# STM32.net
KiCad netlist of a schematic drawn in Altium Designer
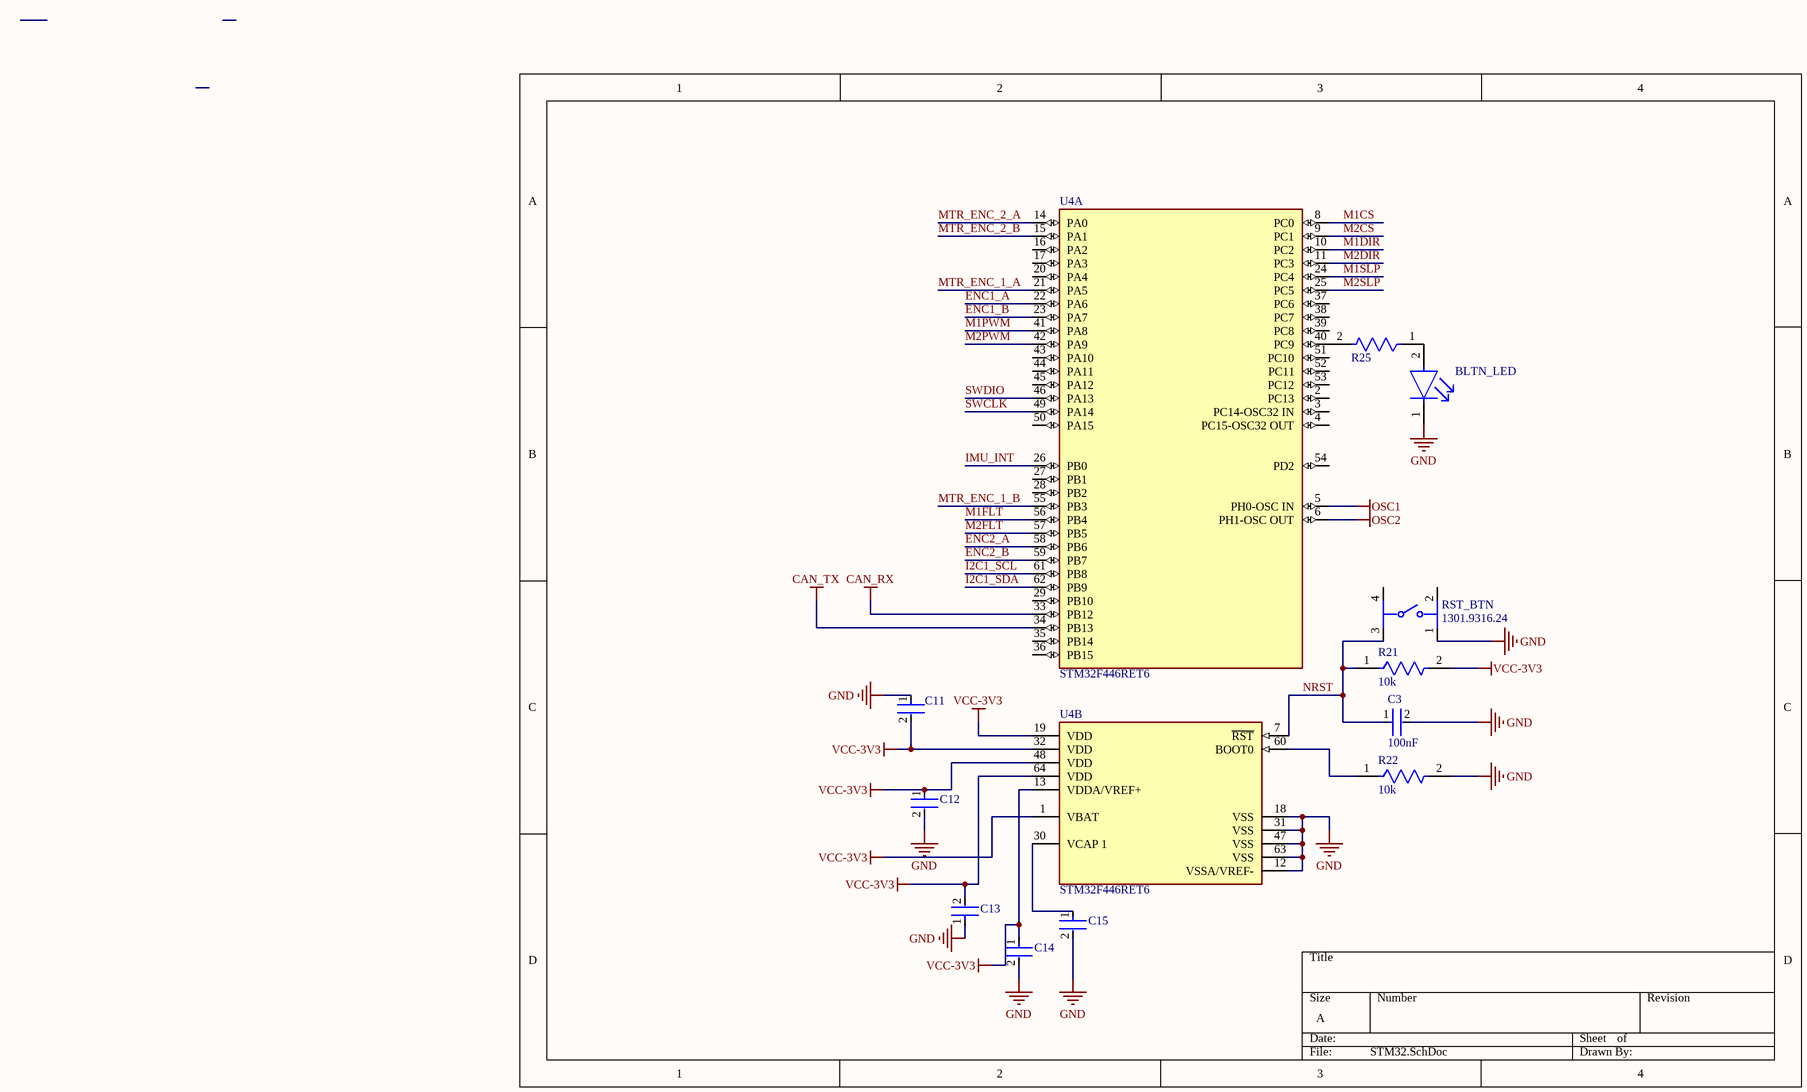
[diagram p0: STM32.SchDoc]

(export (version "E")
  (design (tool "Eeschema 10.0.6"))
  (components
    (comp (ref "BLTN_LED")
      (value "APHCM2012CGCK-F01")
      (footprint "FP-APHCM2012CGCK-F01-MFG")
      (description "LED GREEN CLEAR CHIP SMD")
      (libsource (lib "Altium Content Vault") (part "8706943c75ba83719d021d2fdc84c58"))
    )
    (comp (ref "C3")
      (value "100nF")
      (footprint "FP-0402B104K160CT-IPC_C")
      (description "CAP CER 0.1UF 16V X7R 0402")
      (fields (field (name "TOLERANCE") "10%"))
      (libsource (lib "Altium Content Vault") (part "b4654b650e69147ec39a6b967a45e02"))
    )
    (comp (ref "C11")
      (value "CC0603KRX7R9BB104")
      (footprint "FP-CC0603-DA-MFG")
      (description "CAP CER 0.1UF 50V X7R 0603")
      (fields (field (name "MANUFACTURER") "YAGEO") (field (name "VOLTAGE") "50 V"))
      (libsource (lib "Altium Content Vault") (part "11868f565c42a9108669ba33697ecf6"))
    )
    (comp (ref "C12")
      (value "CC0603KRX7R9BB104")
      (footprint "FP-CC0603-DA-MFG")
      (description "CAP CER 0.1UF 50V X7R 0603")
      (fields (field (name "MANUFACTURER") "YAGEO") (field (name "VOLTAGE") "50 V"))
      (libsource (lib "Altium Content Vault") (part "11868f565c42a9108669ba33697ecf6"))
    )
    (comp (ref "C13")
      (value "CC0603KRX7R9BB104")
      (footprint "FP-CC0603-DA-MFG")
      (description "CAP CER 0.1UF 50V X7R 0603")
      (fields (field (name "MANUFACTURER") "YAGEO") (field (name "VOLTAGE") "50 V"))
      (libsource (lib "Altium Content Vault") (part "11868f565c42a9108669ba33697ecf6"))
    )
    (comp (ref "C14")
      (value "CC0603KRX7R9BB104")
      (footprint "FP-CC0603-DA-MFG")
      (description "CAP CER 0.1UF 50V X7R 0603")
      (fields (field (name "MANUFACTURER") "YAGEO") (field (name "VOLTAGE") "50 V"))
      (libsource (lib "Altium Content Vault") (part "11868f565c42a9108669ba33697ecf6"))
    )
    (comp (ref "C15")
      (value "CL10A475KP8NNNC")
      (footprint "FP-CL10-IPC_C")
      (description "Cap Ceramic 4.7uF 10V X5R ±10% Pad SMD 0603 +85°C T/R")
      (fields (field (name "TOLERANCE") "10%"))
      (libsource (lib "Altium Content Vault") (part "b4654b650e69147ec39a6b967a45e02"))
    )
    (comp (ref "R21")
      (value "10k")
      (footprint "FP-RC0603-0_55-IPC_C")
      (description "RES 10K OHM 1% 1/10W 0603")
      (fields (field (name "TOLERANCE") "1%"))
      (libsource (lib "Altium Content Vault") (part "1029c3af85768c4190bb7ad29bc67b5"))
    )
    (comp (ref "R22")
      (value "10k")
      (footprint "FP-RC0603-0_55-IPC_C")
      (description "RES 10K OHM 1% 1/10W 0603")
      (fields (field (name "TOLERANCE") "1%"))
      (libsource (lib "Altium Content Vault") (part "1029c3af85768c4190bb7ad29bc67b5"))
    )
    (comp (ref "R25")
      (value "AC0603FR-10470RL")
      (footprint "FP-AC0603-IPC_A")
      (description "RES 470Ω 1.00% 0.1W 0603")
      (fields (field (name "TOLERANCE") "1%"))
      (libsource (lib "Altium Content Vault") (part "1029c3af85768c4190bb7ad29bc67b5"))
    )
    (comp (ref "RST_BTN")
      (value "1301.9316.24")
      (footprint "FP-1301_9316_24-MFG")
      (description "LSH 6X6 SHORT TRAVEL SWITCH 7.00")
      (libsource (lib "Altium Content Vault") (part "c0df99d12937e9d2da15afdedf14b17"))
    )
    (comp (ref "U4")
      (value "STM32F446RET6")
      (footprint "FP-LQFP64-5W-MFG")
      (description "IC MCU 32BIT 512KB FLASH 64LQFP")
      (fields
        (field (name "OCTOPART") "https://octopart.com/stm32f446ret6-stmicroelectronics-52642920")
        (field (name "MANUFACTURER") "ST")
      )
      (libsource (lib "Altium Content Vault") (part "ee11adc32c0ab33b933cccf4348c338"))
    )
  )
  (nets
    (net (code "1") (name "/ENC1_A") (class "Default")
      (node (ref "U4") (pin "22") (pinfunction "PA6_22") (pintype "bidirectional"))
    )
    (net (code "2") (name "/ENC1_B") (class "Default")
      (node (ref "U4") (pin "23") (pinfunction "PA7_23") (pintype "bidirectional"))
    )
    (net (code "3") (name "/ENC2_A") (class "Default")
      (node (ref "U4") (pin "58") (pinfunction "PB6_58") (pintype "bidirectional"))
    )
    (net (code "4") (name "/ENC2_B") (class "Default")
      (node (ref "U4") (pin "59") (pinfunction "PB7_59") (pintype "bidirectional"))
    )
    (net (code "5") (name "/I2C1_SCL") (class "Default")
      (node (ref "U4") (pin "61") (pinfunction "PB8_61") (pintype "bidirectional"))
    )
    (net (code "6") (name "/I2C1_SDA") (class "Default")
      (node (ref "U4") (pin "62") (pinfunction "PB9_62") (pintype "bidirectional"))
    )
    (net (code "7") (name "/IMU_INT") (class "Default")
      (node (ref "U4") (pin "26") (pinfunction "PB0_26") (pintype "bidirectional"))
    )
    (net (code "8") (name "/M1CS") (class "Default")
      (node (ref "U4") (pin "8") (pinfunction "PC0_8") (pintype "bidirectional"))
    )
    (net (code "9") (name "/M1DIR") (class "Default")
      (node (ref "U4") (pin "10") (pinfunction "PC2_10") (pintype "bidirectional"))
    )
    (net (code "10") (name "/M1FLT") (class "Default")
      (node (ref "U4") (pin "56") (pinfunction "PB4_56") (pintype "bidirectional"))
    )
    (net (code "11") (name "/M1PWM") (class "Default")
      (node (ref "U4") (pin "41") (pinfunction "PA8_41") (pintype "bidirectional"))
    )
    (net (code "12") (name "/M1SLP") (class "Default")
      (node (ref "U4") (pin "24") (pinfunction "PC4_24") (pintype "bidirectional"))
    )
    (net (code "13") (name "/M2CS") (class "Default")
      (node (ref "U4") (pin "9") (pinfunction "PC1_9") (pintype "bidirectional"))
    )
    (net (code "14") (name "/M2DIR") (class "Default")
      (node (ref "U4") (pin "11") (pinfunction "PC3_11") (pintype "bidirectional"))
    )
    (net (code "15") (name "/M2FLT") (class "Default")
      (node (ref "U4") (pin "57") (pinfunction "PB5_57") (pintype "bidirectional"))
    )
    (net (code "16") (name "/M2PWM") (class "Default")
      (node (ref "U4") (pin "42") (pinfunction "PA9_42") (pintype "bidirectional"))
    )
    (net (code "17") (name "/M2SLP") (class "Default")
      (node (ref "U4") (pin "25") (pinfunction "PC5_25") (pintype "bidirectional"))
    )
    (net (code "18") (name "/MTR_ENC_1_A") (class "Default")
      (node (ref "U4") (pin "21") (pinfunction "PA5_21") (pintype "bidirectional"))
    )
    (net (code "19") (name "/MTR_ENC_1_B") (class "Default")
      (node (ref "U4") (pin "55") (pinfunction "PB3_55") (pintype "bidirectional"))
    )
    (net (code "20") (name "/MTR_ENC_2_A") (class "Default")
      (node (ref "U4") (pin "14") (pinfunction "PA0_14") (pintype "bidirectional"))
    )
    (net (code "21") (name "/MTR_ENC_2_B") (class "Default")
      (node (ref "U4") (pin "15") (pinfunction "PA1_15") (pintype "bidirectional"))
    )
    (net (code "22") (name "/NRST") (class "Default")
      (node (ref "C3") (pin "1") (pinfunction "1_1") (pintype "passive"))
      (node (ref "R21") (pin "1") (pinfunction "1_1") (pintype "passive"))
      (node (ref "RST_BTN") (pin "3") (pinfunction "3_3") (pintype "passive"))
      (node (ref "U4") (pin "7") (pinfunction "~{RST}_7") (pintype "input"))
    )
    (net (code "23") (name "/SWCLK") (class "Default")
      (node (ref "U4") (pin "49") (pinfunction "PA14_49") (pintype "bidirectional"))
    )
    (net (code "24") (name "/SWDIO") (class "Default")
      (node (ref "U4") (pin "46") (pinfunction "PA13_46") (pintype "bidirectional"))
    )
    (net (code "25") (name "CAN_RX") (class "Default")
      (node (ref "U4") (pin "33") (pinfunction "PB12_33") (pintype "bidirectional"))
    )
    (net (code "26") (name "CAN_TX") (class "Default")
      (node (ref "U4") (pin "34") (pinfunction "PB13_34") (pintype "bidirectional"))
    )
    (net (code "27") (name "GND") (class "Default")
      (node (ref "BLTN_LED") (pin "1") (pinfunction "C_1") (pintype "passive"))
      (node (ref "C11") (pin "1") (pinfunction "1_1") (pintype "passive"))
      (node (ref "C12") (pin "2") (pinfunction "2_2") (pintype "passive"))
      (node (ref "C13") (pin "1") (pinfunction "1_1") (pintype "passive"))
      (node (ref "C14") (pin "2") (pinfunction "2_2") (pintype "passive"))
      (node (ref "C15") (pin "2") (pinfunction "2_2") (pintype "passive"))
      (node (ref "C3") (pin "2") (pinfunction "2_2") (pintype "passive"))
      (node (ref "R22") (pin "2") (pinfunction "2_2") (pintype "passive"))
      (node (ref "RST_BTN") (pin "1") (pinfunction "1_1") (pintype "passive"))
      (node (ref "U4") (pin "12") (pinfunction "VSSA/VREF-_12") (pintype "power_in"))
      (node (ref "U4") (pin "18") (pinfunction "VSS_18") (pintype "power_in"))
      (node (ref "U4") (pin "31") (pinfunction "VSS_31") (pintype "power_in"))
      (node (ref "U4") (pin "47") (pinfunction "VSS_47") (pintype "power_in"))
      (node (ref "U4") (pin "63") (pinfunction "VSS_63") (pintype "power_in"))
    )
    (net (code "28") (name "Net-(BLTN_LED-A)") (class "Default")
      (node (ref "BLTN_LED") (pin "2") (pinfunction "A_2") (pintype "passive"))
      (node (ref "R25") (pin "1") (pinfunction "1_1") (pintype "passive"))
    )
    (net (code "29") (name "Net-(U4A-PC9)") (class "Default")
      (node (ref "R25") (pin "2") (pinfunction "2_2") (pintype "passive"))
      (node (ref "U4") (pin "40") (pinfunction "PC9_40") (pintype "bidirectional"))
    )
    (net (code "30") (name "Net-(U4B-BOOT0)") (class "Default")
      (node (ref "R22") (pin "1") (pinfunction "1_1") (pintype "passive"))
      (node (ref "U4") (pin "60") (pinfunction "BOOT0_60") (pintype "input"))
    )
    (net (code "31") (name "Net-(U4B-VCAP_1)") (class "Default")
      (node (ref "C15") (pin "1") (pinfunction "1_1") (pintype "passive"))
      (node (ref "U4") (pin "30") (pinfunction "VCAP_1_30") (pintype "power_in"))
    )
    (net (code "32") (name "OSC1") (class "Default")
      (node (ref "U4") (pin "5") (pinfunction "PH0-OSC_IN_5") (pintype "bidirectional"))
    )
    (net (code "33") (name "OSC2") (class "Default")
      (node (ref "U4") (pin "6") (pinfunction "PH1-OSC_OUT_6") (pintype "bidirectional"))
    )
    (net (code "34") (name "VCC-3V3") (class "Default")
      (node (ref "C11") (pin "2") (pinfunction "2_2") (pintype "passive"))
      (node (ref "C12") (pin "1") (pinfunction "1_1") (pintype "passive"))
      (node (ref "C13") (pin "2") (pinfunction "2_2") (pintype "passive"))
      (node (ref "C14") (pin "1") (pinfunction "1_1") (pintype "passive"))
      (node (ref "R21") (pin "2") (pinfunction "2_2") (pintype "passive"))
      (node (ref "U4") (pin "1") (pinfunction "VBAT_1") (pintype "power_in"))
      (node (ref "U4") (pin "13") (pinfunction "VDDA/VREF+_13") (pintype "power_in"))
      (node (ref "U4") (pin "19") (pinfunction "VDD_19") (pintype "power_in"))
      (node (ref "U4") (pin "32") (pinfunction "VDD_32") (pintype "power_in"))
      (node (ref "U4") (pin "48") (pinfunction "VDD_48") (pintype "power_in"))
      (node (ref "U4") (pin "64") (pinfunction "VDD_64") (pintype "power_in"))
    )
    (net (code "35") (name "unconnected-(RST_BTN-Pad2)") (class "Default")
      (node (ref "RST_BTN") (pin "2") (pinfunction "2_2") (pintype "passive"))
    )
    (net (code "36") (name "unconnected-(RST_BTN-Pad4)") (class "Default")
      (node (ref "RST_BTN") (pin "4") (pinfunction "4_4") (pintype "passive"))
    )
    (net (code "37") (name "unconnected-(U4A-PA2-Pad16)") (class "Default")
      (node (ref "U4") (pin "16") (pinfunction "PA2_16") (pintype "bidirectional"))
    )
    (net (code "38") (name "unconnected-(U4A-PA3-Pad17)") (class "Default")
      (node (ref "U4") (pin "17") (pinfunction "PA3_17") (pintype "bidirectional"))
    )
    (net (code "39") (name "unconnected-(U4A-PA4-Pad20)") (class "Default")
      (node (ref "U4") (pin "20") (pinfunction "PA4_20") (pintype "bidirectional"))
    )
    (net (code "40") (name "unconnected-(U4A-PA10-Pad43)") (class "Default")
      (node (ref "U4") (pin "43") (pinfunction "PA10_43") (pintype "bidirectional"))
    )
    (net (code "41") (name "unconnected-(U4A-PA11-Pad44)") (class "Default")
      (node (ref "U4") (pin "44") (pinfunction "PA11_44") (pintype "bidirectional"))
    )
    (net (code "42") (name "unconnected-(U4A-PA12-Pad45)") (class "Default")
      (node (ref "U4") (pin "45") (pinfunction "PA12_45") (pintype "bidirectional"))
    )
    (net (code "43") (name "unconnected-(U4A-PA15-Pad50)") (class "Default")
      (node (ref "U4") (pin "50") (pinfunction "PA15_50") (pintype "bidirectional"))
    )
    (net (code "44") (name "unconnected-(U4A-PB1-Pad27)") (class "Default")
      (node (ref "U4") (pin "27") (pinfunction "PB1_27") (pintype "bidirectional"))
    )
    (net (code "45") (name "unconnected-(U4A-PB2-Pad28)") (class "Default")
      (node (ref "U4") (pin "28") (pinfunction "PB2_28") (pintype "bidirectional"))
    )
    (net (code "46") (name "unconnected-(U4A-PB10-Pad29)") (class "Default")
      (node (ref "U4") (pin "29") (pinfunction "PB10_29") (pintype "bidirectional"))
    )
    (net (code "47") (name "unconnected-(U4A-PB14-Pad35)") (class "Default")
      (node (ref "U4") (pin "35") (pinfunction "PB14_35") (pintype "bidirectional"))
    )
    (net (code "48") (name "unconnected-(U4A-PB15-Pad36)") (class "Default")
      (node (ref "U4") (pin "36") (pinfunction "PB15_36") (pintype "bidirectional"))
    )
    (net (code "49") (name "unconnected-(U4A-PC6-Pad37)") (class "Default")
      (node (ref "U4") (pin "37") (pinfunction "PC6_37") (pintype "bidirectional"))
    )
    (net (code "50") (name "unconnected-(U4A-PC7-Pad38)") (class "Default")
      (node (ref "U4") (pin "38") (pinfunction "PC7_38") (pintype "bidirectional"))
    )
    (net (code "51") (name "unconnected-(U4A-PC8-Pad39)") (class "Default")
      (node (ref "U4") (pin "39") (pinfunction "PC8_39") (pintype "bidirectional"))
    )
    (net (code "52") (name "unconnected-(U4A-PC10-Pad51)") (class "Default")
      (node (ref "U4") (pin "51") (pinfunction "PC10_51") (pintype "bidirectional"))
    )
    (net (code "53") (name "unconnected-(U4A-PC11-Pad52)") (class "Default")
      (node (ref "U4") (pin "52") (pinfunction "PC11_52") (pintype "bidirectional"))
    )
    (net (code "54") (name "unconnected-(U4A-PC12-Pad53)") (class "Default")
      (node (ref "U4") (pin "53") (pinfunction "PC12_53") (pintype "bidirectional"))
    )
    (net (code "55") (name "unconnected-(U4A-PC13-Pad2)") (class "Default")
      (node (ref "U4") (pin "2") (pinfunction "PC13_2") (pintype "bidirectional"))
    )
    (net (code "56") (name "unconnected-(U4A-PC14-OSC32_IN-Pad3)") (class "Default")
      (node (ref "U4") (pin "3") (pinfunction "PC14-OSC32_IN_3") (pintype "bidirectional"))
    )
    (net (code "57") (name "unconnected-(U4A-PC15-OSC32_OUT-Pad4)") (class "Default")
      (node (ref "U4") (pin "4") (pinfunction "PC15-OSC32_OUT_4") (pintype "bidirectional"))
    )
    (net (code "58") (name "unconnected-(U4A-PD2-Pad54)") (class "Default")
      (node (ref "U4") (pin "54") (pinfunction "PD2_54") (pintype "bidirectional"))
    )
  )
)
